# 18-Power-P3V3.net
KiCad netlist of a schematic drawn in Altium Designer
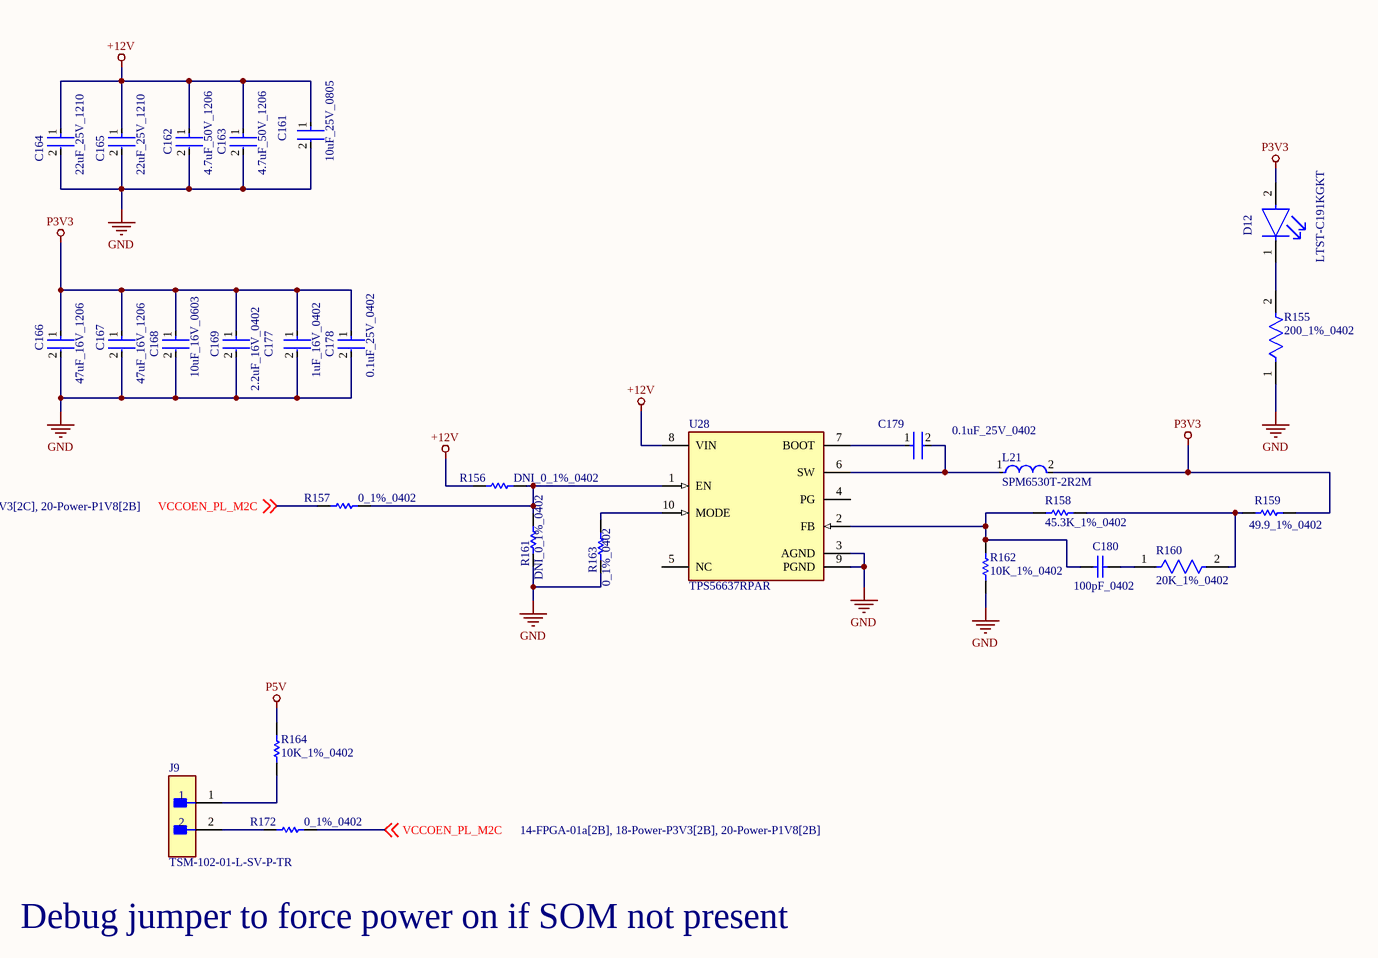
[diagram p0: 18-Power-P3V3.SchDoc]

(export (version "E")
  (design (tool "Eeschema 10.0.6"))
  (components
    (comp (ref "C161")
      (value "10uF_25V_0805")
      (footprint "FP-0805-L_2_0_0_2-W_1_25-MFG")
      (description "Multilayer Ceramic Capacitor 10uF 25V X5R 10% SMD 0805 T/R")
      (fields (field (name "VOLTAGE") "16V") (field (name "TOLERANCE") "10%"))
      (libsource (lib "Altium Content Vault") (part "02cd4be3c70576c341d710602a673aa"))
    )
    (comp (ref "C162")
      (value "4.7uF_50V_1206")
      (footprint "FP-GRM31C-0_2-e0_3_0_8-IPC_C")
      (description "Chip Multilayer Ceramic Capacitors for General Purpose, 1206, 4.7uF, X7R, 15%, 10%, 50V")
      (fields (field (name "VOLTAGE") "50V") (field (name "TOLERANCE") "10%"))
      (libsource (lib "Altium Content Vault") (part "02cd4be3c70576c341d710602a673aa"))
    )
    (comp (ref "C163")
      (value "4.7uF_50V_1206")
      (footprint "FP-GRM31C-0_2-e0_3_0_8-IPC_C")
      (description "Chip Multilayer Ceramic Capacitors for General Purpose, 1206, 4.7uF, X7R, 15%, 10%, 50V")
      (fields (field (name "VOLTAGE") "50V") (field (name "TOLERANCE") "10%"))
      (libsource (lib "Altium Content Vault") (part "02cd4be3c70576c341d710602a673aa"))
    )
    (comp (ref "C164")
      (value "22uF_25V_1210")
      (footprint "FP-MK325M-MFG")
      (description "CAP CER 22UF 25V X5R 1210")
      (fields (field (name "TOLERANCE") "20%"))
      (libsource (lib "Altium Content Vault") (part "b4654b650e69147ec39a6b967a45e02"))
    )
    (comp (ref "C165")
      (value "22uF_25V_1210")
      (footprint "FP-MK325M-MFG")
      (description "CAP CER 22UF 25V X5R 1210")
      (fields (field (name "TOLERANCE") "20%"))
      (libsource (lib "Altium Content Vault") (part "b4654b650e69147ec39a6b967a45e02"))
    )
    (comp (ref "C166")
      (value "47uF_16V_1206")
      (footprint "FP-C3216-160-0_2-MFG")
      (description "Multilayer Ceramic Capacitors 47uF ±20% 16V X5R SMD 1206")
      (fields (field (name "TOLERANCE") "20%"))
      (libsource (lib "Altium Content Vault") (part "11868f565c42a9108669ba33697ecf6"))
    )
    (comp (ref "C167")
      (value "47uF_16V_1206")
      (footprint "FP-C3216-160-0_2-MFG")
      (description "Multilayer Ceramic Capacitors 47uF ±20% 16V X5R SMD 1206")
      (fields (field (name "TOLERANCE") "20%"))
      (libsource (lib "Altium Content Vault") (part "11868f565c42a9108669ba33697ecf6"))
    )
    (comp (ref "C168")
      (value "10uF_16V_0603")
      (footprint "FP-0603-L_1_6_0_2-W_0_8_0-MFG")
      (description "Multilayer Ceramic Capacitor 10uF 16V X5R 20% SMD 0603 T/R")
      (fields (field (name "TOLERANCE") "20%"))
      (libsource (lib "Altium Content Vault") (part "b4654b650e69147ec39a6b967a45e02"))
    )
    (comp (ref "C169")
      (value "2.2uF_16V_0402")
      (footprint "FP-C1005-050-0_05-IPC_A")
      (description "Multilayer Ceramic Capacitors 2.2μF ±10% 16V X5R SMD 0402")
      (fields (field (name "TOLERANCE") "10%"))
      (libsource (lib "Altium Content Vault") (part "b4654b650e69147ec39a6b967a45e02"))
    )
    (comp (ref "C177")
      (value "1uF_16V_0402")
      (footprint "FP-0402-L_1_0_0_05-W_0_5-IPC_A")
      (description "None")
      (fields (field (name "TOLERANCE") "10%"))
      (libsource (lib "Altium Content Vault") (part "b4654b650e69147ec39a6b967a45e02"))
    )
    (comp (ref "C178")
      (value "0.1uF_25V_0402")
      (footprint "FP-0402-L_1_0_1-W_0_5_0_1-IPC_C")
      (description "General Purpose Ceramic Capacitor, 0402, 100nF, 10%, X7R, 15%, 25V")
      (fields (field (name "VOLTAGE") "25V") (field (name "TOLERANCE") "10%"))
      (libsource (lib "Altium Content Vault") (part "b4654b650e69147ec39a6b967a45e02"))
    )
    (comp (ref "C179")
      (value "0.1uF_25V_0402")
      (footprint "FP-0402-L_1_0_1-W_0_5_0_1-IPC_C")
      (description "General Purpose Ceramic Capacitor, 0402, 100nF, 10%, X7R, 15%, 25V")
      (fields (field (name "VOLTAGE") "25V") (field (name "TOLERANCE") "10%"))
      (libsource (lib "Altium Content Vault") (part "b4654b650e69147ec39a6b967a45e02"))
    )
    (comp (ref "C180")
      (value "100pF_0402")
      (footprint "CAPC1005X55X25ML05T10")
      (fields (field (name "MANUFACTURER") "Murata") (field (name "PART NUMBER") "GRM1555C1H101JA01D"))
      (libsource (lib "Altium Content Vault") (part "CAP"))
    )
    (comp (ref "D12")
      (value "LTST-C191KGKT")
      (footprint "FP-LTST-C191KGKT-MFG")
      (description "LED GREEN CLEAR SMD")
      (libsource (lib "Altium Content Vault") (part "8706943c75ba83719d021d2fdc84c58"))
    )
    (comp (ref "J9")
      (value "TSM-102-01-L-SV-P-TR")
      (footprint "FP-TSM-102-01-L-SV-P-TR-MFG")
      (description "CONN HEADER SMD 2POS 2.54MM")
      (libsource (lib "Altium Content Vault") (part "3bc925449376181038e59eaffc5286c"))
    )
    (comp (ref "L21")
      (value "SPM6530T-2R2M")
      (footprint "FP-SPM6530-MFG")
      (description "FIXED IND 2.2UH 8.2A 19 MOHM SMD")
      (fields
        (field (name "OCTOPART") "https://octopart.com/spm6530t-2r2m-tdk-18903909")
        (field (name "MANUFACTURER") "TDK")
      )
      (libsource (lib "Altium Content Vault") (part "725321dda6339637d4d059423bc1c3c"))
    )
    (comp (ref "R155")
      (value "200_1%_0402")
      (footprint "FP-ERJ2RK-IPC_A")
      (description "RES SMD 200 OHM 1% 1/10W 0402")
      (fields (field (name "TOLERANCE") "1%"))
      (libsource (lib "Altium Content Vault") (part "1029c3af85768c4190bb7ad29bc67b5"))
    )
    (comp (ref "R156")
      (value "DNI_0_1%_0402")
      (footprint "RESC1005X40X25LL05T05")
      (description "Chip Resistor, 0 Ohm, 0.1 W, -55 to 155 degC, 0402 (1005 Metric), RoHS, Tape and Reel")
      (fields (field (name "MANUFACTURER") "Panasonic") (field (name "TOLERANCE") "5%"))
      (libsource (lib "Altium Content Vault") (part "RES-2"))
    )
    (comp (ref "R157")
      (value "0_1%_0402")
      (footprint "RESC1005X40X25LL05T05")
      (description "Chip Resistor, 0 Ohm, 0.1 W, -55 to 155 degC, 0402 (1005 Metric), RoHS, Tape and Reel")
      (fields (field (name "MANUFACTURER") "Panasonic") (field (name "TOLERANCE") "5%"))
      (libsource (lib "Altium Content Vault") (part "RES-2"))
    )
    (comp (ref "R158")
      (value "45.3K_1%_0402")
      (footprint "RESC1005X40X25ML05T05")
      (fields (field (name "PART NUMBER") "ERJ-2RKF4532X") (field (name "MANUFACTURER") "Panasonic"))
      (libsource (lib "Altium Content Vault") (part "RES"))
    )
    (comp (ref "R159")
      (value "49.9_1%_0402")
      (footprint "RESC1005X40X25LL05T10")
      (fields (field (name "MANUFACTURER") "Yageo / Phycomp") (field (name "PART NUMBER") "RC0402FR-0749R9L"))
      (libsource (lib "Altium Content Vault") (part "RES"))
    )
    (comp (ref "R160")
      (value "20K_1%_0402")
      (footprint "FP-ERJ2RK-MFG")
      (description "RES SMD 20K OHM 1% 1/10W 0402")
      (fields (field (name "TOLERANCE") "1%"))
      (libsource (lib "Altium Content Vault") (part "1029c3af85768c4190bb7ad29bc67b5"))
    )
    (comp (ref "R161")
      (value "DNI_0_1%_0402")
      (footprint "RESC1005X40X25LL05T05")
      (description "Chip Resistor, 0 Ohm, 0.1 W, -55 to 155 degC, 0402 (1005 Metric), RoHS, Tape and Reel")
      (fields (field (name "MANUFACTURER") "Panasonic") (field (name "TOLERANCE") "5%"))
      (libsource (lib "Altium Content Vault") (part "RES-2"))
    )
    (comp (ref "R162")
      (value "10K_1%_0402")
      (footprint "RESC1005X40X25LL05T05")
      (description "Chip Resistor, 10 KOhm, +/- 1%, 0.1 W, -55 to 155 degC, 0402 (1005 Metric), RoHS, Tape and Reel")
      (fields (field (name "TOLERANCE") "1%") (field (name "MANUFACTURER") "Panasonic"))
      (libsource (lib "Altium Content Vault") (part "RES-2"))
    )
    (comp (ref "R163")
      (value "0_1%_0402")
      (footprint "RESC1005X40X25LL05T05")
      (description "Chip Resistor, 0 Ohm, 0.1 W, -55 to 155 degC, 0402 (1005 Metric), RoHS, Tape and Reel")
      (fields (field (name "MANUFACTURER") "Panasonic") (field (name "TOLERANCE") "5%"))
      (libsource (lib "Altium Content Vault") (part "RES-2"))
    )
    (comp (ref "R164")
      (value "10K_1%_0402")
      (footprint "RESC1005X40X25LL05T05")
      (description "Chip Resistor, 10 KOhm, +/- 1%, 0.1 W, -55 to 155 degC, 0402 (1005 Metric), RoHS, Tape and Reel")
      (fields (field (name "TOLERANCE") "1%") (field (name "MANUFACTURER") "Panasonic"))
      (libsource (lib "Altium Content Vault") (part "RES-2"))
    )
    (comp (ref "R172")
      (value "0_1%_0402")
      (footprint "RESC1005X40X25LL05T05")
      (description "Chip Resistor, 0 Ohm, 0.1 W, -55 to 155 degC, 0402 (1005 Metric), RoHS, Tape and Reel")
      (fields (field (name "MANUFACTURER") "Panasonic") (field (name "TOLERANCE") "5%"))
      (libsource (lib "Altium Content Vault") (part "RES-2"))
    )
    (comp (ref "U28")
      (value "TPS56637RPAR")
      (footprint "FP-RPA0010A-MFG")
      (description "IC POWER MANAGEMENT")
      (fields
        (field (name "OCTOPART") "https://octopart.com/tps56637rpar-texas+instruments-97650653")
        (field (name "MANUFACTURER") "Texas Instruments")
      )
      (libsource (lib "Altium Content Vault") (part "31007e10bcfaaa9b7385bfd54c3e755"))
    )
  )
  (nets
    (net (code "1") (name "+12V") (class "Default")
      (node (ref "C161") (pin "1") (pinfunction "1_1") (pintype "passive"))
      (node (ref "C162") (pin "1") (pinfunction "1_1") (pintype "passive"))
      (node (ref "C163") (pin "1") (pinfunction "1_1") (pintype "passive"))
      (node (ref "C164") (pin "1") (pinfunction "1_1") (pintype "passive"))
      (node (ref "C165") (pin "1") (pinfunction "1_1") (pintype "passive"))
      (node (ref "R156") (pin "1") (pinfunction "1_1") (pintype "passive"))
      (node (ref "U28") (pin "8") (pinfunction "VIN_8") (pintype "power_in"))
    )
    (net (code "2") (name "GND") (class "Default")
      (node (ref "C161") (pin "2") (pinfunction "2_2") (pintype "passive"))
      (node (ref "C162") (pin "2") (pinfunction "2_2") (pintype "passive"))
      (node (ref "C163") (pin "2") (pinfunction "2_2") (pintype "passive"))
      (node (ref "C164") (pin "2") (pinfunction "2_2") (pintype "passive"))
      (node (ref "C165") (pin "2") (pinfunction "2_2") (pintype "passive"))
      (node (ref "C166") (pin "2") (pinfunction "2_2") (pintype "passive"))
      (node (ref "C167") (pin "2") (pinfunction "2_2") (pintype "passive"))
      (node (ref "C168") (pin "2") (pinfunction "2_2") (pintype "passive"))
      (node (ref "C169") (pin "2") (pinfunction "2_2") (pintype "passive"))
      (node (ref "C177") (pin "2") (pinfunction "2_2") (pintype "passive"))
      (node (ref "C178") (pin "2") (pinfunction "2_2") (pintype "passive"))
      (node (ref "R155") (pin "1") (pinfunction "1_1") (pintype "passive"))
      (node (ref "R161") (pin "1") (pinfunction "1_1") (pintype "passive"))
      (node (ref "R162") (pin "1") (pinfunction "1_1") (pintype "passive"))
      (node (ref "R163") (pin "1") (pinfunction "1_1") (pintype "passive"))
      (node (ref "U28") (pin "3") (pinfunction "AGND_3") (pintype "power_in"))
      (node (ref "U28") (pin "9") (pinfunction "PGND_9") (pintype "power_in"))
    )
    (net (code "3") (name "Net-(C180-Pad2)") (class "Default")
      (node (ref "C180") (pin "2") (pinfunction "2_2") (pintype "passive"))
      (node (ref "R160") (pin "1") (pinfunction "1_1") (pintype "passive"))
    )
    (net (code "4") (name "Net-(D12-C)") (class "Default")
      (node (ref "D12") (pin "1") (pinfunction "C_1") (pintype "passive"))
      (node (ref "R155") (pin "2") (pinfunction "2_2") (pintype "passive"))
    )
    (net (code "5") (name "Net-(J9-Pad1)") (class "Default")
      (node (ref "J9") (pin "1") (pinfunction "1_1") (pintype "passive"))
      (node (ref "R164") (pin "1") (pinfunction "1_1") (pintype "passive"))
    )
    (net (code "6") (name "Net-(J9-Pad2)") (class "Default")
      (node (ref "J9") (pin "2") (pinfunction "2_2") (pintype "passive"))
      (node (ref "R172") (pin "1") (pinfunction "1_1") (pintype "passive"))
    )
    (net (code "7") (name "Net-(R158-Pad2)") (class "Default")
      (node (ref "R158") (pin "2") (pinfunction "2_2") (pintype "passive"))
      (node (ref "R159") (pin "1") (pinfunction "1_1") (pintype "passive"))
      (node (ref "R160") (pin "2") (pinfunction "2_2") (pintype "passive"))
    )
    (net (code "8") (name "Net-(U28-BOOT)") (class "Default")
      (node (ref "C179") (pin "1") (pinfunction "1_1") (pintype "passive"))
      (node (ref "U28") (pin "7") (pinfunction "BOOT_7") (pintype "power_in"))
    )
    (net (code "9") (name "Net-(U28-EN)") (class "Default")
      (node (ref "R156") (pin "2") (pinfunction "2_2") (pintype "passive"))
      (node (ref "R157") (pin "2") (pinfunction "2_2") (pintype "passive"))
      (node (ref "R161") (pin "2") (pinfunction "2_2") (pintype "passive"))
      (node (ref "U28") (pin "1") (pinfunction "EN_1") (pintype "input"))
    )
    (net (code "10") (name "Net-(U28-FB)") (class "Default")
      (node (ref "C180") (pin "1") (pinfunction "1_1") (pintype "passive"))
      (node (ref "R158") (pin "1") (pinfunction "1_1") (pintype "passive"))
      (node (ref "R162") (pin "2") (pinfunction "2_2") (pintype "passive"))
      (node (ref "U28") (pin "2") (pinfunction "FB_2") (pintype "input"))
    )
    (net (code "11") (name "Net-(U28-MODE)") (class "Default")
      (node (ref "R163") (pin "2") (pinfunction "2_2") (pintype "passive"))
      (node (ref "U28") (pin "10") (pinfunction "MODE_10") (pintype "input"))
    )
    (net (code "12") (name "Net-(U28-SW)") (class "Default")
      (node (ref "C179") (pin "2") (pinfunction "2_2") (pintype "passive"))
      (node (ref "L21") (pin "1") (pinfunction "1_1") (pintype "passive"))
      (node (ref "U28") (pin "6") (pinfunction "SW_6") (pintype "power_in"))
    )
    (net (code "13") (name "P3V3") (class "Default")
      (node (ref "C166") (pin "1") (pinfunction "1_1") (pintype "passive"))
      (node (ref "C167") (pin "1") (pinfunction "1_1") (pintype "passive"))
      (node (ref "C168") (pin "1") (pinfunction "1_1") (pintype "passive"))
      (node (ref "C169") (pin "1") (pinfunction "1_1") (pintype "passive"))
      (node (ref "C177") (pin "1") (pinfunction "1_1") (pintype "passive"))
      (node (ref "C178") (pin "1") (pinfunction "1_1") (pintype "passive"))
      (node (ref "D12") (pin "2") (pinfunction "A_2") (pintype "passive"))
      (node (ref "L21") (pin "2") (pinfunction "2_2") (pintype "passive"))
      (node (ref "R159") (pin "2") (pinfunction "2_2") (pintype "passive"))
    )
    (net (code "14") (name "P5V") (class "Default")
      (node (ref "R164") (pin "2") (pinfunction "2_2") (pintype "passive"))
    )
    (net (code "15") (name "VCCOEN_PL_M2C") (class "Default")
      (node (ref "R157") (pin "1") (pinfunction "1_1") (pintype "passive"))
      (node (ref "R172") (pin "2") (pinfunction "2_2") (pintype "passive"))
    )
    (net (code "16") (name "unconnected-(U28-NC-Pad5)") (class "Default")
      (node (ref "U28") (pin "5") (pinfunction "NC_5") (pintype "passive"))
    )
    (net (code "17") (name "unconnected-(U28-PG-Pad4)") (class "Default")
      (node (ref "U28") (pin "4") (pinfunction "PG_4") (pintype "open_collector"))
    )
  )
)
